# hexbot.net
KiCad netlist of a schematic drawn in Altium Designer
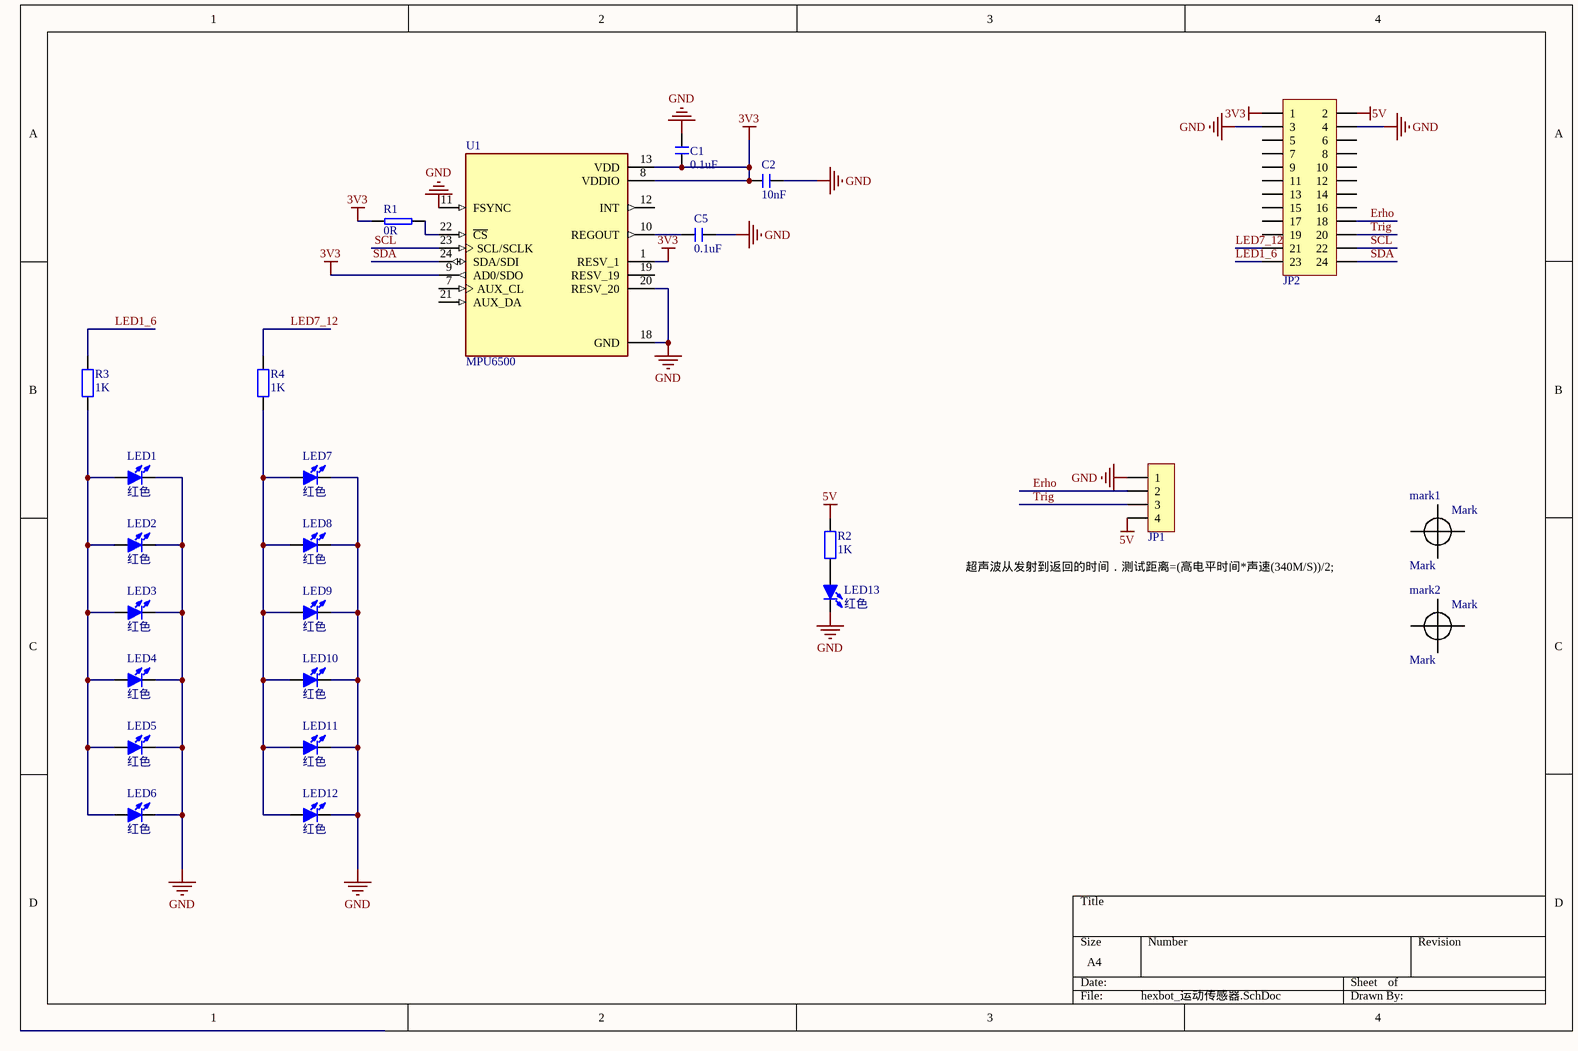
[diagram p0: hexbot_运动传感器.SchDoc]

(export (version "E")
  (design (tool "Eeschema 10.0.6"))
  (components
    (comp (ref "C1")
      (value "0.1uF")
      (footprint "C 0603_L")
      (description "贴片电容")
      (libsource (lib "0.1 - 电阻-电容-电感") (part "C"))
    )
    (comp (ref "C2")
      (value "10nF")
      (footprint "C 0603_L")
      (description "贴片电容")
      (libsource (lib "0.1 - 电阻-电容-电感") (part "C"))
    )
    (comp (ref "C5")
      (value "0.1uF")
      (footprint "C 0603_L")
      (description "贴片电容")
      (libsource (lib "0.1 - 电阻-电容-电感") (part "C"))
    )
    (comp (ref "JP1")
      (value "HDR-1X4")
      (footprint "HDR2.54-LI-4P")
      (description "4P接插件")
      (fields (field (name "版权归属") "封装库来自淘宝 ID：黄晶宝石"))
      (libsource (lib "5.4 - 接插件-脚距2.54 (100mil) ") (part "Header 4"))
    )
    (comp (ref "JP2")
      (value "Header 2X11")
      (footprint "HDR2.54-WI-2x12P")
      (description "12*2P接插件")
      (fields (field (name "版权归属") "封装库来自淘宝卖家 ID：黄晶宝石"))
      (libsource (lib "5.4 - 接插件-脚距2.54 (100mil) ") (part "Header 12X2"))
    )
    (comp (ref "LED1")
      (value "红色")
      (footprint "LED 0603R")
      (description "贴片LED")
      (fields (field (name "版权归属") "封装库来自淘宝 ID：黄晶宝石"))
      (libsource (lib "0.3 - LED发光二极管") (part "LED-SMD"))
    )
    (comp (ref "LED2")
      (value "红色")
      (footprint "LED 0603R")
      (description "贴片LED")
      (fields (field (name "版权归属") "封装库来自淘宝 ID：黄晶宝石"))
      (libsource (lib "0.3 - LED发光二极管") (part "LED-SMD"))
    )
    (comp (ref "LED3")
      (value "红色")
      (footprint "LED 0603R")
      (description "贴片LED")
      (fields (field (name "版权归属") "封装库来自淘宝 ID：黄晶宝石"))
      (libsource (lib "0.3 - LED发光二极管") (part "LED-SMD"))
    )
    (comp (ref "LED4")
      (value "红色")
      (footprint "LED 0603R")
      (description "贴片LED")
      (fields (field (name "版权归属") "封装库来自淘宝 ID：黄晶宝石"))
      (libsource (lib "0.3 - LED发光二极管") (part "LED-SMD"))
    )
    (comp (ref "LED5")
      (value "红色")
      (footprint "LED 0603R")
      (description "贴片LED")
      (fields (field (name "版权归属") "封装库来自淘宝 ID：黄晶宝石"))
      (libsource (lib "0.3 - LED发光二极管") (part "LED-SMD"))
    )
    (comp (ref "LED6")
      (value "红色")
      (footprint "LED 0603R")
      (description "贴片LED")
      (fields (field (name "版权归属") "封装库来自淘宝 ID：黄晶宝石"))
      (libsource (lib "0.3 - LED发光二极管") (part "LED-SMD"))
    )
    (comp (ref "LED7")
      (value "红色")
      (footprint "LED 0603R")
      (description "贴片LED")
      (fields (field (name "版权归属") "封装库来自淘宝 ID：黄晶宝石"))
      (libsource (lib "0.3 - LED发光二极管") (part "LED-SMD"))
    )
    (comp (ref "LED8")
      (value "红色")
      (footprint "LED 0603R")
      (description "贴片LED")
      (fields (field (name "版权归属") "封装库来自淘宝 ID：黄晶宝石"))
      (libsource (lib "0.3 - LED发光二极管") (part "LED-SMD"))
    )
    (comp (ref "LED9")
      (value "红色")
      (footprint "LED 0603R")
      (description "贴片LED")
      (fields (field (name "版权归属") "封装库来自淘宝 ID：黄晶宝石"))
      (libsource (lib "0.3 - LED发光二极管") (part "LED-SMD"))
    )
    (comp (ref "LED10")
      (value "红色")
      (footprint "LED 0603R")
      (description "贴片LED")
      (fields (field (name "版权归属") "封装库来自淘宝 ID：黄晶宝石"))
      (libsource (lib "0.3 - LED发光二极管") (part "LED-SMD"))
    )
    (comp (ref "LED11")
      (value "红色")
      (footprint "LED 0603R")
      (description "贴片LED")
      (fields (field (name "版权归属") "封装库来自淘宝 ID：黄晶宝石"))
      (libsource (lib "0.3 - LED发光二极管") (part "LED-SMD"))
    )
    (comp (ref "LED12")
      (value "红色")
      (footprint "LED 0603R")
      (description "贴片LED")
      (fields (field (name "版权归属") "封装库来自淘宝 ID：黄晶宝石"))
      (libsource (lib "0.3 - LED发光二极管") (part "LED-SMD"))
    )
    (comp (ref "LED13")
      (value "红色")
      (footprint "LED 0603R")
      (description "贴片LED")
      (fields (field (name "版权归属") "封装库来自淘宝 ID：黄晶宝石"))
      (libsource (lib "0.3 - LED发光二极管") (part "LED-SMD"))
    )
    (comp (ref "mark1") (value "Mark") (footprint "Mark:Mark") (libsource (lib "Mark") (part "Mark")))
    (comp (ref "mark2") (value "Mark") (footprint "Mark:Mark") (libsource (lib "Mark") (part "Mark")))
    (comp (ref "R1") (value "0R") (footprint "0603") (libsource (lib "*") (part "RES2")))
    (comp (ref "R2")
      (value "1K")
      (footprint "R 0805_L")
      (description "贴片电阻")
      (fields (field (name "版权归属") "来自淘宝 ID：黄晶宝石"))
      (libsource (lib "0.1 - 电阻-电容-电感") (part "R"))
    )
    (comp (ref "R3")
      (value "1K")
      (footprint "R 0603_L")
      (description "贴片电阻")
      (fields (field (name "版权归属") "来自淘宝 ID：黄晶宝石"))
      (libsource (lib "0.1 - 电阻-电容-电感") (part "R"))
    )
    (comp (ref "R4")
      (value "1K")
      (footprint "R 0603_L")
      (description "贴片电阻")
      (fields (field (name "版权归属") "来自淘宝 ID：黄晶宝石"))
      (libsource (lib "0.1 - 电阻-电容-电感") (part "R"))
    )
    (comp (ref "U1")
      (value "MPU6500")
      (footprint "MPU-6050")
      (description "Accelerometer, Gyroscope, Magnetometer, 9 Axis Sensor IÂ²C, SPI Output")
      (fields (field (name "MP") "MPU-9250") (field (name "MF") "TDK InvenSense"))
      (libsource (lib "RvStar") (part "MPU-9250"))
    )
  )
  (nets
    (net (code "1") (name "/Erho") (class "Default")
      (node (ref "JP1") (pin "2") (pinfunction "2_2") (pintype "passive"))
      (node (ref "JP2") (pin "18") (pinfunction "18_18") (pintype "passive"))
    )
    (net (code "2") (name "/LED1_6") (class "Default")
      (node (ref "JP2") (pin "23") (pinfunction "23_23") (pintype "passive"))
      (node (ref "R3") (pin "2") (pinfunction "2_2") (pintype "passive"))
    )
    (net (code "3") (name "/LED7_12") (class "Default")
      (node (ref "JP2") (pin "21") (pinfunction "21_21") (pintype "passive"))
      (node (ref "R4") (pin "2") (pinfunction "2_2") (pintype "passive"))
    )
    (net (code "4") (name "/SCL") (class "Default")
      (node (ref "JP2") (pin "22") (pinfunction "22_22") (pintype "passive"))
      (node (ref "U1") (pin "23") (pinfunction "SCL/SCLK_23") (pintype "input"))
    )
    (net (code "5") (name "/SDA") (class "Default")
      (node (ref "JP2") (pin "24") (pinfunction "24_24") (pintype "passive"))
      (node (ref "U1") (pin "24") (pinfunction "SDA/SDI_24") (pintype "bidirectional"))
    )
    (net (code "6") (name "/Trig") (class "Default")
      (node (ref "JP1") (pin "3") (pinfunction "3_3") (pintype "passive"))
      (node (ref "JP2") (pin "20") (pinfunction "20_20") (pintype "passive"))
    )
    (net (code "7") (name "3V3") (class "Default")
      (node (ref "C1") (pin "2") (pinfunction "2_2") (pintype "passive"))
      (node (ref "C2") (pin "2") (pinfunction "2_2") (pintype "passive"))
      (node (ref "JP2") (pin "1") (pinfunction "1_1") (pintype "passive"))
      (node (ref "R1") (pin "1") (pinfunction "1_1") (pintype "passive"))
      (node (ref "U1") (pin "1") (pinfunction "RESV_1_1") (pintype "passive"))
      (node (ref "U1") (pin "13") (pinfunction "VDD_13") (pintype "power_in"))
      (node (ref "U1") (pin "8") (pinfunction "VDDIO_8") (pintype "power_in"))
      (node (ref "U1") (pin "9") (pinfunction "AD0/SDO_9") (pintype "output"))
    )
    (net (code "8") (name "5V") (class "Default")
      (node (ref "JP1") (pin "4") (pinfunction "4_4") (pintype "passive"))
      (node (ref "JP2") (pin "2") (pinfunction "2_2") (pintype "passive"))
      (node (ref "R2") (pin "2") (pinfunction "2_2") (pintype "passive"))
    )
    (net (code "9") (name "GND") (class "Default")
      (node (ref "C1") (pin "1") (pinfunction "1_1") (pintype "passive"))
      (node (ref "C2") (pin "1") (pinfunction "1_1") (pintype "passive"))
      (node (ref "C5") (pin "1") (pinfunction "1_1") (pintype "passive"))
      (node (ref "JP1") (pin "1") (pinfunction "1_1") (pintype "passive"))
      (node (ref "JP2") (pin "3") (pinfunction "3_3") (pintype "passive"))
      (node (ref "JP2") (pin "4") (pinfunction "4_4") (pintype "passive"))
      (node (ref "LED1") (pin "2") (pinfunction "K_2") (pintype "passive"))
      (node (ref "LED10") (pin "2") (pinfunction "K_2") (pintype "passive"))
      (node (ref "LED11") (pin "2") (pinfunction "K_2") (pintype "passive"))
      (node (ref "LED12") (pin "2") (pinfunction "K_2") (pintype "passive"))
      (node (ref "LED13") (pin "2") (pinfunction "K_2") (pintype "passive"))
      (node (ref "LED2") (pin "2") (pinfunction "K_2") (pintype "passive"))
      (node (ref "LED3") (pin "2") (pinfunction "K_2") (pintype "passive"))
      (node (ref "LED4") (pin "2") (pinfunction "K_2") (pintype "passive"))
      (node (ref "LED5") (pin "2") (pinfunction "K_2") (pintype "passive"))
      (node (ref "LED6") (pin "2") (pinfunction "K_2") (pintype "passive"))
      (node (ref "LED7") (pin "2") (pinfunction "K_2") (pintype "passive"))
      (node (ref "LED8") (pin "2") (pinfunction "K_2") (pintype "passive"))
      (node (ref "LED9") (pin "2") (pinfunction "K_2") (pintype "passive"))
      (node (ref "U1") (pin "11") (pinfunction "FSYNC_11") (pintype "input"))
      (node (ref "U1") (pin "18") (pinfunction "GND_18") (pintype "power_in"))
      (node (ref "U1") (pin "20") (pinfunction "RESV_20_20") (pintype "passive"))
    )
    (net (code "10") (name "Net-(LED1-A)") (class "Default")
      (node (ref "LED1") (pin "1") (pinfunction "A_1") (pintype "passive"))
      (node (ref "LED2") (pin "1") (pinfunction "A_1") (pintype "passive"))
      (node (ref "LED3") (pin "1") (pinfunction "A_1") (pintype "passive"))
      (node (ref "LED4") (pin "1") (pinfunction "A_1") (pintype "passive"))
      (node (ref "LED5") (pin "1") (pinfunction "A_1") (pintype "passive"))
      (node (ref "LED6") (pin "1") (pinfunction "A_1") (pintype "passive"))
      (node (ref "R3") (pin "1") (pinfunction "1_1") (pintype "passive"))
    )
    (net (code "11") (name "Net-(LED10-A)") (class "Default")
      (node (ref "LED10") (pin "1") (pinfunction "A_1") (pintype "passive"))
      (node (ref "LED11") (pin "1") (pinfunction "A_1") (pintype "passive"))
      (node (ref "LED12") (pin "1") (pinfunction "A_1") (pintype "passive"))
      (node (ref "LED7") (pin "1") (pinfunction "A_1") (pintype "passive"))
      (node (ref "LED8") (pin "1") (pinfunction "A_1") (pintype "passive"))
      (node (ref "LED9") (pin "1") (pinfunction "A_1") (pintype "passive"))
      (node (ref "R4") (pin "1") (pinfunction "1_1") (pintype "passive"))
    )
    (net (code "12") (name "Net-(LED13-A)") (class "Default")
      (node (ref "LED13") (pin "1") (pinfunction "A_1") (pintype "passive"))
      (node (ref "R2") (pin "1") (pinfunction "1_1") (pintype "passive"))
    )
    (net (code "13") (name "Net-(U1-REGOUT)") (class "Default")
      (node (ref "C5") (pin "2") (pinfunction "2_2") (pintype "passive"))
      (node (ref "U1") (pin "10") (pinfunction "REGOUT_10") (pintype "output"))
    )
    (net (code "14") (name "Net-(U1-~{CS})") (class "Default")
      (node (ref "R1") (pin "2") (pinfunction "2_2") (pintype "passive"))
      (node (ref "U1") (pin "22") (pinfunction "~{CS}_22") (pintype "input"))
    )
    (net (code "15") (name "unconnected-(JP2-Pad5)") (class "Default")
      (node (ref "JP2") (pin "5") (pinfunction "5_5") (pintype "passive"))
    )
    (net (code "16") (name "unconnected-(JP2-Pad6)") (class "Default")
      (node (ref "JP2") (pin "6") (pinfunction "6_6") (pintype "passive"))
    )
    (net (code "17") (name "unconnected-(JP2-Pad7)") (class "Default")
      (node (ref "JP2") (pin "7") (pinfunction "7_7") (pintype "passive"))
    )
    (net (code "18") (name "unconnected-(JP2-Pad8)") (class "Default")
      (node (ref "JP2") (pin "8") (pinfunction "8_8") (pintype "passive"))
    )
    (net (code "19") (name "unconnected-(JP2-Pad9)") (class "Default")
      (node (ref "JP2") (pin "9") (pinfunction "9_9") (pintype "passive"))
    )
    (net (code "20") (name "unconnected-(JP2-Pad10)") (class "Default")
      (node (ref "JP2") (pin "10") (pinfunction "10_10") (pintype "passive"))
    )
    (net (code "21") (name "unconnected-(JP2-Pad11)") (class "Default")
      (node (ref "JP2") (pin "11") (pinfunction "11_11") (pintype "passive"))
    )
    (net (code "22") (name "unconnected-(JP2-Pad12)") (class "Default")
      (node (ref "JP2") (pin "12") (pinfunction "12_12") (pintype "passive"))
    )
    (net (code "23") (name "unconnected-(JP2-Pad13)") (class "Default")
      (node (ref "JP2") (pin "13") (pinfunction "13_13") (pintype "passive"))
    )
    (net (code "24") (name "unconnected-(JP2-Pad14)") (class "Default")
      (node (ref "JP2") (pin "14") (pinfunction "14_14") (pintype "passive"))
    )
    (net (code "25") (name "unconnected-(JP2-Pad15)") (class "Default")
      (node (ref "JP2") (pin "15") (pinfunction "15_15") (pintype "passive"))
    )
    (net (code "26") (name "unconnected-(JP2-Pad16)") (class "Default")
      (node (ref "JP2") (pin "16") (pinfunction "16_16") (pintype "passive"))
    )
    (net (code "27") (name "unconnected-(JP2-Pad17)") (class "Default")
      (node (ref "JP2") (pin "17") (pinfunction "17_17") (pintype "passive"))
    )
    (net (code "28") (name "unconnected-(JP2-Pad19)") (class "Default")
      (node (ref "JP2") (pin "19") (pinfunction "19_19") (pintype "passive"))
    )
    (net (code "29") (name "unconnected-(U1-AUX_CL-Pad7)") (class "Default")
      (node (ref "U1") (pin "7") (pinfunction "AUX_CL_7") (pintype "input"))
    )
    (net (code "30") (name "unconnected-(U1-AUX_DA-Pad21)") (class "Default")
      (node (ref "U1") (pin "21") (pinfunction "AUX_DA_21") (pintype "input"))
    )
    (net (code "31") (name "unconnected-(U1-INT-Pad12)") (class "Default")
      (node (ref "U1") (pin "12") (pinfunction "INT_12") (pintype "output"))
    )
    (net (code "32") (name "unconnected-(U1-RESV_19-Pad19)") (class "Default")
      (node (ref "U1") (pin "19") (pinfunction "RESV_19_19") (pintype "passive"))
    )
  )
)
